# Thermostat_EEM_Breakout.net
KiCad netlist of a schematic drawn in Altium Designer
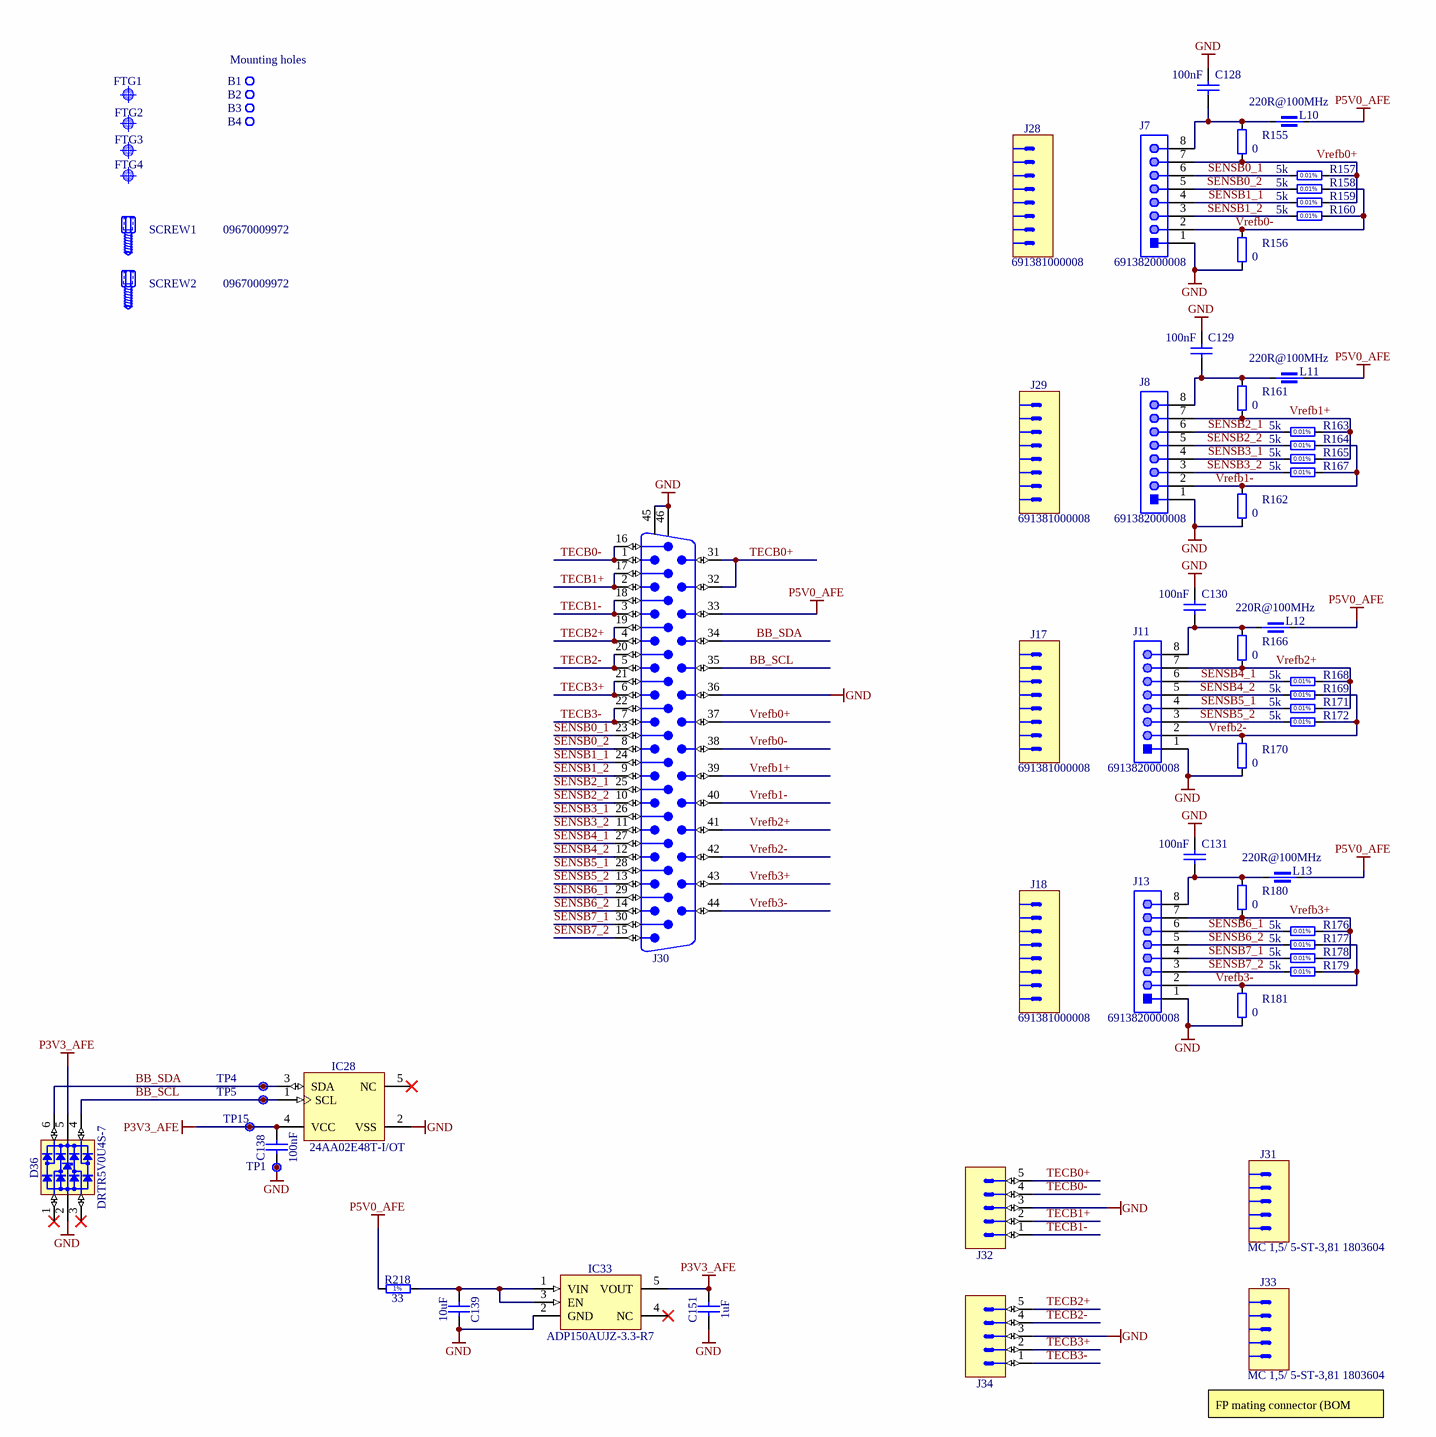
[diagram p0: Thermostat_EEM_Breakout.SchDoc]

(export (version "E")
  (design (tool "Eeschema 10.0.6"))
  (components
    (comp (ref "B1")
      (value "Plated Hole")
      (footprint "MTG320_550")
      (description "Single Terminal Socket")
      (fields (field (name "PART NUMBER") "PLATED_HOLE3.2_PAD5.5") (field (name "AUTHOR") "CERN DEM JMW"))
      (libsource (lib "Eletro-mechanical") (part "Single Terminal Socket"))
    )
    (comp (ref "B2")
      (value "Plated Hole")
      (footprint "MTG320_550")
      (description "Single Terminal Socket")
      (fields (field (name "PART NUMBER") "PLATED_HOLE3.2_PAD5.5") (field (name "AUTHOR") "CERN DEM JMW"))
      (libsource (lib "Eletro-mechanical") (part "Single Terminal Socket"))
    )
    (comp (ref "B3")
      (value "Plated Hole")
      (footprint "MTG320_550")
      (description "Single Terminal Socket")
      (fields (field (name "PART NUMBER") "PLATED_HOLE3.2_PAD5.5") (field (name "AUTHOR") "CERN DEM JMW"))
      (libsource (lib "Eletro-mechanical") (part "Single Terminal Socket"))
    )
    (comp (ref "B4")
      (value "Plated Hole")
      (footprint "MTG320_550")
      (description "Single Terminal Socket")
      (fields (field (name "PART NUMBER") "PLATED_HOLE3.2_PAD5.5") (field (name "AUTHOR") "CERN DEM JMW"))
      (libsource (lib "Eletro-mechanical") (part "Single Terminal Socket"))
    )
    (comp (ref "C128")
      (value "100nF")
      (footprint "CAPC1005X55N")
      (description "Non-polarised capacitor")
      (fields
        (field (name "PART NUMBER") "CC0402_100NF_16V_10%_X5R")
        (field (name "VOLTAGE") "16V")
        (field (name "AUTHOR") "CERN DEM JLC")
      )
      (libsource (lib "Capacitors") (part "Capacitor - non polarized"))
    )
    (comp (ref "C129")
      (value "100nF")
      (footprint "CAPC1005X55N")
      (description "Non-polarised capacitor")
      (fields
        (field (name "PART NUMBER") "CC0402_100NF_16V_10%_X5R")
        (field (name "VOLTAGE") "16V")
        (field (name "AUTHOR") "CERN DEM JLC")
      )
      (libsource (lib "Capacitors") (part "Capacitor - non polarized"))
    )
    (comp (ref "C130")
      (value "100nF")
      (footprint "CAPC1005X55N")
      (description "Non-polarised capacitor")
      (fields
        (field (name "PART NUMBER") "CC0402_100NF_16V_10%_X5R")
        (field (name "VOLTAGE") "16V")
        (field (name "AUTHOR") "CERN DEM JLC")
      )
      (libsource (lib "Capacitors") (part "Capacitor - non polarized"))
    )
    (comp (ref "C131")
      (value "100nF")
      (footprint "CAPC1005X55N")
      (description "Non-polarised capacitor")
      (fields
        (field (name "PART NUMBER") "CC0402_100NF_16V_10%_X5R")
        (field (name "VOLTAGE") "16V")
        (field (name "AUTHOR") "CERN DEM JLC")
      )
      (libsource (lib "Capacitors") (part "Capacitor - non polarized"))
    )
    (comp (ref "C138")
      (value "100nF")
      (footprint "CAPC1005X55N")
      (description "Non-polarised capacitor")
      (fields
        (field (name "PART NUMBER") "CC0402_100NF_16V_10%_X5R")
        (field (name "VOLTAGE") "16V")
        (field (name "AUTHOR") "CERN DEM JLC")
      )
      (libsource (lib "Capacitors") (part "Capacitor - non polarized"))
    )
    (comp (ref "C139")
      (value "10uF")
      (footprint "CAPC2012X135N")
      (description "Non-polarised capacitor")
      (fields
        (field (name "PART NUMBER") "CC0805_10UF_16V_10%_X5R")
        (field (name "VOLTAGE") "16V")
        (field (name "AUTHOR") "CERN DEM JLC")
      )
      (libsource (lib "Capacitors") (part "Capacitor - non polarized"))
    )
    (comp (ref "C151")
      (value "1uF")
      (footprint "CAPC1608X87N")
      (description "Non-polarised capacitor")
      (fields
        (field (name "PART NUMBER") "CC0603_1UF_25V_10%_X7R")
        (field (name "VOLTAGE") "25V")
        (field (name "AUTHOR") "CERN DEM JLC")
      )
      (libsource (lib "Capacitors") (part "Capacitor - non polarized"))
    )
    (comp (ref "D36")
      (value "DRTR5V0U4S-7")
      (footprint "SOT65P210X110-6N")
      (description "Integrated Quad Ultra-Low Capacitance ESD Protection")
      (fields (field (name "MANUFACTURER") "DIODES") (field (name "AUTHOR") "GK"))
      (libsource (lib "Diodes") (part "D_TVS_DRTR5V0U4S-7"))
    )
    (comp (ref "FTG1")
      (value "Use only in PCB")
      (footprint "FIDUCIAL_TOP_S100-200")
      (description "Fiducial Target")
      (fields (field (name "PART NUMBER") "FIDUCIAL_TARGET_S100-200") (field (name "AUTHOR") "CERN DEM JLC"))
      (libsource (lib "Eletro-mechanical") (part "Fiducial Target"))
    )
    (comp (ref "FTG2")
      (value "Use only in PCB")
      (footprint "FIDUCIAL_TOP_S100-200")
      (description "Fiducial Target")
      (fields (field (name "PART NUMBER") "FIDUCIAL_TARGET_S100-200") (field (name "AUTHOR") "CERN DEM JLC"))
      (libsource (lib "Eletro-mechanical") (part "Fiducial Target"))
    )
    (comp (ref "FTG3")
      (value "Use only in PCB")
      (footprint "FIDUCIAL_TOP_S100-200")
      (description "Fiducial Target")
      (fields (field (name "PART NUMBER") "FIDUCIAL_TARGET_S100-200") (field (name "AUTHOR") "CERN DEM JLC"))
      (libsource (lib "Eletro-mechanical") (part "Fiducial Target"))
    )
    (comp (ref "FTG4")
      (value "Use only in PCB")
      (footprint "FIDUCIAL_TOP_S100-200")
      (description "Fiducial Target")
      (fields (field (name "PART NUMBER") "FIDUCIAL_TARGET_S100-200") (field (name "AUTHOR") "CERN DEM JLC"))
      (libsource (lib "Eletro-mechanical") (part "Fiducial Target"))
    )
    (comp (ref "IC28")
      (value "24AA02E48T-I/OT")
      (footprint "SOT95P280X145-5N")
      (description "1.7V-5.5V, 2K I2C Serial EEPROM With EUI-48 Node Identity")
      (fields (field (name "MANUFACTURER") "MICROCHIP TECHNOLOGY") (field (name "AUTHOR") "CERN DEM MR"))
      (libsource (lib "ICs And Semiconductors") (part "24AA02E48T-I/OT"))
    )
    (comp (ref "IC33")
      (value "ADP150AUJZ-3.3-R7")
      (footprint "SOT95P280X90-5N")
      (description "Ultralow Noise, 150 mA CMOS Linear Regulator")
      (fields (field (name "MANUFACTURER") "ANALOG DEVICES") (field (name "AUTHOR") "CERN DEM JLC"))
      (libsource (lib "ICs And Semiconductors") (part "ADP150AUJZ"))
    )
    (comp (ref "J7")
      (value "691382000008")
      (footprint "691382000008")
      (description "WR-TBL Serie 382 Vertical PCB Header, Pluggable, pitch 2.5mm, 8p")
      (fields (field (name "PUBLISHER") "Wurth Elektronik"))
      (libsource (lib "Altium_WR-TBL (rev19a)") (part "691382000008"))
    )
    (comp (ref "J8")
      (value "691382000008")
      (footprint "691382000008")
      (description "WR-TBL Serie 382 Vertical PCB Header, Pluggable, pitch 2.5mm, 8p")
      (fields (field (name "PUBLISHER") "Wurth Elektronik"))
      (libsource (lib "Altium_WR-TBL (rev19a)") (part "691382000008"))
    )
    (comp (ref "J11")
      (value "691382000008")
      (footprint "691382000008")
      (description "WR-TBL Serie 382 Vertical PCB Header, Pluggable, pitch 2.5mm, 8p")
      (fields (field (name "PUBLISHER") "Wurth Elektronik"))
      (libsource (lib "Altium_WR-TBL (rev19a)") (part "691382000008"))
    )
    (comp (ref "J13")
      (value "691382000008")
      (footprint "691382000008")
      (description "WR-TBL Serie 382 Vertical PCB Header, Pluggable, pitch 2.5mm, 8p")
      (fields (field (name "PUBLISHER") "Wurth Elektronik"))
      (libsource (lib "Altium_WR-TBL (rev19a)") (part "691382000008"))
    )
    (comp (ref "J17")
      (value "691381000008")
      (footprint "WURTH_691381000008")
      (description "Phoenix Contact 2.5 pitch terminal plug, 8 ways")
      (fields (field (name "MANUFACTURER") "WURTH") (field (name "MANUFACTURER PART NUMBER") "691381000008"))
      (libsource (lib "Connectors") (part "CON_TB_WURTH_691381000008"))
    )
    (comp (ref "J18")
      (value "691381000008")
      (footprint "WURTH_691381000008")
      (description "Phoenix Contact 2.5 pitch terminal plug, 8 ways")
      (fields (field (name "MANUFACTURER") "WURTH") (field (name "MANUFACTURER PART NUMBER") "691381000008"))
      (libsource (lib "Connectors") (part "CON_TB_WURTH_691381000008"))
    )
    (comp (ref "J28")
      (value "691381000008")
      (footprint "WURTH_691381000008")
      (description "Phoenix Contact 2.5 pitch terminal plug, 8 ways")
      (fields (field (name "MANUFACTURER") "WURTH") (field (name "MANUFACTURER PART NUMBER") "691381000008"))
      (libsource (lib "Connectors") (part "CON_TB_WURTH_691381000008"))
    )
    (comp (ref "J29")
      (value "691381000008")
      (footprint "WURTH_691381000008")
      (description "Phoenix Contact 2.5 pitch terminal plug, 8 ways")
      (fields (field (name "MANUFACTURER") "WURTH") (field (name "MANUFACTURER PART NUMBER") "691381000008"))
      (libsource (lib "Connectors") (part "CON_TB_WURTH_691381000008"))
    )
    (comp (ref "J30")
      (value "D-Sub")
      (footprint "AMPHENOL_10090926-P444XLF")
      (description "Connector D-sub 44 Male")
      (fields
        (field (name "PART NUMBER") "AMPHENOL_10090926-P444XLF")
        (field (name "MANUFACTURER") "AMPHENOL")
        (field (name "AUTHOR") "CERN DEM BC")
      )
      (libsource (lib "Connectors") (part "Connector D-sub 44 Male"))
    )
    (comp (ref "J31")
      (value "~")
      (footprint "PHOENIX_1803604")
      (description "Phoenix Contact 3.81 pitch terminal plug, 5 ways")
      (fields
        (field (name "MANUFACTURER") "Phoenix Contact")
        (field (name "MANUFACTURER PART NUMBER") "MC 1,5/ 5-ST-3,81 1803604")
      )
      (libsource (lib "Connectors") (part "PHOENIX_1803604"))
    )
    (comp (ref "J32")
      (value "~")
      (footprint "PHOENIX_1803455")
      (description "Connector 5 Male")
      (fields
        (field (name "PART NUMBER") "PHOENIX_1803455")
        (field (name "MANUFACTURER") "PHOENIX CONTACT")
        (field (name "AUTHOR") "CERN DEM JLC")
      )
      (libsource (lib "Connectors") (part "Connector 5 Male"))
    )
    (comp (ref "J33")
      (value "~")
      (footprint "PHOENIX_1803604")
      (description "Phoenix Contact 3.81 pitch terminal plug, 5 ways")
      (fields
        (field (name "MANUFACTURER") "Phoenix Contact")
        (field (name "MANUFACTURER PART NUMBER") "MC 1,5/ 5-ST-3,81 1803604")
      )
      (libsource (lib "Connectors") (part "PHOENIX_1803604"))
    )
    (comp (ref "J34")
      (value "~")
      (footprint "PHOENIX_1803455")
      (description "Connector 5 Male")
      (fields
        (field (name "PART NUMBER") "PHOENIX_1803455")
        (field (name "MANUFACTURER") "PHOENIX CONTACT")
        (field (name "AUTHOR") "CERN DEM JLC")
      )
      (libsource (lib "Connectors") (part "Connector 5 Male"))
    )
    (comp (ref "L10")
      (value "220R@100MHz")
      (footprint "INDC1005X55N")
      (fields
        (field (name "PART NUMBER") "IND0402_MURATA_BLM15HB221SN1")
        (field (name "POWER") "250mA")
        (field (name "TOLERANCE") "±25%")
        (field (name "AUTHOR") "CERN DEM JLC")
      )
      (libsource (lib "Inductors & Transformers") (part "Ferrite Bead"))
    )
    (comp (ref "L11")
      (value "220R@100MHz")
      (footprint "INDC1005X55N")
      (fields
        (field (name "PART NUMBER") "IND0402_MURATA_BLM15HB221SN1")
        (field (name "POWER") "250mA")
        (field (name "TOLERANCE") "±25%")
        (field (name "AUTHOR") "CERN DEM JLC")
      )
      (libsource (lib "Inductors & Transformers") (part "Ferrite Bead"))
    )
    (comp (ref "L12")
      (value "220R@100MHz")
      (footprint "INDC1005X55N")
      (fields
        (field (name "PART NUMBER") "IND0402_MURATA_BLM15HB221SN1")
        (field (name "POWER") "250mA")
        (field (name "TOLERANCE") "±25%")
        (field (name "AUTHOR") "CERN DEM JLC")
      )
      (libsource (lib "Inductors & Transformers") (part "Ferrite Bead"))
    )
    (comp (ref "L13")
      (value "220R@100MHz")
      (footprint "INDC1005X55N")
      (fields
        (field (name "PART NUMBER") "IND0402_MURATA_BLM15HB221SN1")
        (field (name "POWER") "250mA")
        (field (name "TOLERANCE") "±25%")
        (field (name "AUTHOR") "CERN DEM JLC")
      )
      (libsource (lib "Inductors & Transformers") (part "Ferrite Bead"))
    )
    (comp (ref "R155")
      (value "0")
      (footprint "RESC1608X55N")
      (description "Resistor")
      (fields
        (field (name "PART NUMBER") "R0603_0R_JUMPER")
        (field (name "MANUFACTURER") "GENERIC")
        (field (name "AUTHOR") "CERN DEM JLC")
      )
      (libsource (lib "Resistors") (part "Resistor"))
    )
    (comp (ref "R156")
      (value "0")
      (footprint "RESC1608X55N")
      (description "Resistor")
      (fields
        (field (name "PART NUMBER") "R0603_0R_JUMPER")
        (field (name "MANUFACTURER") "GENERIC")
        (field (name "AUTHOR") "CERN DEM JLC")
      )
      (libsource (lib "Resistors") (part "Resistor"))
    )
    (comp (ref "R157")
      (value "5k")
      (footprint "RESC2013X64N")
      (description "Resistor - 0.01%")
      (fields
        (field (name "PART NUMBER") "R0805_5K_0.01%_0.2W_0.2PPM_VISHAY_VSMP")
        (field (name "POWER") "0.2W")
        (field (name "AUTHOR") "CERN DEM JLC")
      )
      (libsource (lib "Resistors") (part "Resistor - 0.01%"))
    )
    (comp (ref "R158")
      (value "5k")
      (footprint "RESC2013X64N")
      (description "Resistor - 0.01%")
      (fields
        (field (name "PART NUMBER") "R0805_5K_0.01%_0.2W_0.2PPM_VISHAY_VSMP")
        (field (name "POWER") "0.2W")
        (field (name "AUTHOR") "CERN DEM JLC")
      )
      (libsource (lib "Resistors") (part "Resistor - 0.01%"))
    )
    (comp (ref "R159")
      (value "5k")
      (footprint "RESC2013X64N")
      (description "Resistor - 0.01%")
      (fields
        (field (name "PART NUMBER") "R0805_5K_0.01%_0.2W_0.2PPM_VISHAY_VSMP")
        (field (name "POWER") "0.2W")
        (field (name "AUTHOR") "CERN DEM JLC")
      )
      (libsource (lib "Resistors") (part "Resistor - 0.01%"))
    )
    (comp (ref "R160")
      (value "5k")
      (footprint "RESC2013X64N")
      (description "Resistor - 0.01%")
      (fields
        (field (name "PART NUMBER") "R0805_5K_0.01%_0.2W_0.2PPM_VISHAY_VSMP")
        (field (name "POWER") "0.2W")
        (field (name "AUTHOR") "CERN DEM JLC")
      )
      (libsource (lib "Resistors") (part "Resistor - 0.01%"))
    )
    (comp (ref "R161")
      (value "0")
      (footprint "RESC1608X55N")
      (description "Resistor")
      (fields
        (field (name "PART NUMBER") "R0603_0R_JUMPER")
        (field (name "MANUFACTURER") "GENERIC")
        (field (name "AUTHOR") "CERN DEM JLC")
      )
      (libsource (lib "Resistors") (part "Resistor"))
    )
    (comp (ref "R162")
      (value "0")
      (footprint "RESC1608X55N")
      (description "Resistor")
      (fields
        (field (name "PART NUMBER") "R0603_0R_JUMPER")
        (field (name "MANUFACTURER") "GENERIC")
        (field (name "AUTHOR") "CERN DEM JLC")
      )
      (libsource (lib "Resistors") (part "Resistor"))
    )
    (comp (ref "R163")
      (value "5k")
      (footprint "RESC2013X64N")
      (description "Resistor - 0.01%")
      (fields
        (field (name "PART NUMBER") "R0805_5K_0.01%_0.2W_0.2PPM_VISHAY_VSMP")
        (field (name "POWER") "0.2W")
        (field (name "AUTHOR") "CERN DEM JLC")
      )
      (libsource (lib "Resistors") (part "Resistor - 0.01%"))
    )
    (comp (ref "R164")
      (value "5k")
      (footprint "RESC2013X64N")
      (description "Resistor - 0.01%")
      (fields
        (field (name "PART NUMBER") "R0805_5K_0.01%_0.2W_0.2PPM_VISHAY_VSMP")
        (field (name "POWER") "0.2W")
        (field (name "AUTHOR") "CERN DEM JLC")
      )
      (libsource (lib "Resistors") (part "Resistor - 0.01%"))
    )
    (comp (ref "R165")
      (value "5k")
      (footprint "RESC2013X64N")
      (description "Resistor - 0.01%")
      (fields
        (field (name "PART NUMBER") "R0805_5K_0.01%_0.2W_0.2PPM_VISHAY_VSMP")
        (field (name "POWER") "0.2W")
        (field (name "AUTHOR") "CERN DEM JLC")
      )
      (libsource (lib "Resistors") (part "Resistor - 0.01%"))
    )
    (comp (ref "R166")
      (value "0")
      (footprint "RESC1608X55N")
      (description "Resistor")
      (fields
        (field (name "PART NUMBER") "R0603_0R_JUMPER")
        (field (name "MANUFACTURER") "GENERIC")
        (field (name "AUTHOR") "CERN DEM JLC")
      )
      (libsource (lib "Resistors") (part "Resistor"))
    )
    (comp (ref "R167")
      (value "5k")
      (footprint "RESC2013X64N")
      (description "Resistor - 0.01%")
      (fields
        (field (name "PART NUMBER") "R0805_5K_0.01%_0.2W_0.2PPM_VISHAY_VSMP")
        (field (name "POWER") "0.2W")
        (field (name "AUTHOR") "CERN DEM JLC")
      )
      (libsource (lib "Resistors") (part "Resistor - 0.01%"))
    )
    (comp (ref "R168")
      (value "5k")
      (footprint "RESC2013X64N")
      (description "Resistor - 0.01%")
      (fields
        (field (name "PART NUMBER") "R0805_5K_0.01%_0.2W_0.2PPM_VISHAY_VSMP")
        (field (name "POWER") "0.2W")
        (field (name "AUTHOR") "CERN DEM JLC")
      )
      (libsource (lib "Resistors") (part "Resistor - 0.01%"))
    )
    (comp (ref "R169")
      (value "5k")
      (footprint "RESC2013X64N")
      (description "Resistor - 0.01%")
      (fields
        (field (name "PART NUMBER") "R0805_5K_0.01%_0.2W_0.2PPM_VISHAY_VSMP")
        (field (name "POWER") "0.2W")
        (field (name "AUTHOR") "CERN DEM JLC")
      )
      (libsource (lib "Resistors") (part "Resistor - 0.01%"))
    )
    (comp (ref "R170")
      (value "0")
      (footprint "RESC1608X55N")
      (description "Resistor")
      (fields
        (field (name "PART NUMBER") "R0603_0R_JUMPER")
        (field (name "MANUFACTURER") "GENERIC")
        (field (name "AUTHOR") "CERN DEM JLC")
      )
      (libsource (lib "Resistors") (part "Resistor"))
    )
    (comp (ref "R171")
      (value "5k")
      (footprint "RESC2013X64N")
      (description "Resistor - 0.01%")
      (fields
        (field (name "PART NUMBER") "R0805_5K_0.01%_0.2W_0.2PPM_VISHAY_VSMP")
        (field (name "POWER") "0.2W")
        (field (name "AUTHOR") "CERN DEM JLC")
      )
      (libsource (lib "Resistors") (part "Resistor - 0.01%"))
    )
    (comp (ref "R172")
      (value "5k")
      (footprint "RESC2013X64N")
      (description "Resistor - 0.01%")
      (fields
        (field (name "PART NUMBER") "R0805_5K_0.01%_0.2W_0.2PPM_VISHAY_VSMP")
        (field (name "POWER") "0.2W")
        (field (name "AUTHOR") "CERN DEM JLC")
      )
      (libsource (lib "Resistors") (part "Resistor - 0.01%"))
    )
    (comp (ref "R176")
      (value "5k")
      (footprint "RESC2013X64N")
      (description "Resistor - 0.01%")
      (fields
        (field (name "PART NUMBER") "R0805_5K_0.01%_0.2W_0.2PPM_VISHAY_VSMP")
        (field (name "POWER") "0.2W")
        (field (name "AUTHOR") "CERN DEM JLC")
      )
      (libsource (lib "Resistors") (part "Resistor - 0.01%"))
    )
    (comp (ref "R177")
      (value "5k")
      (footprint "RESC2013X64N")
      (description "Resistor - 0.01%")
      (fields
        (field (name "PART NUMBER") "R0805_5K_0.01%_0.2W_0.2PPM_VISHAY_VSMP")
        (field (name "POWER") "0.2W")
        (field (name "AUTHOR") "CERN DEM JLC")
      )
      (libsource (lib "Resistors") (part "Resistor - 0.01%"))
    )
    (comp (ref "R178")
      (value "5k")
      (footprint "RESC2013X64N")
      (description "Resistor - 0.01%")
      (fields
        (field (name "PART NUMBER") "R0805_5K_0.01%_0.2W_0.2PPM_VISHAY_VSMP")
        (field (name "POWER") "0.2W")
        (field (name "AUTHOR") "CERN DEM JLC")
      )
      (libsource (lib "Resistors") (part "Resistor - 0.01%"))
    )
    (comp (ref "R179")
      (value "5k")
      (footprint "RESC2013X64N")
      (description "Resistor - 0.01%")
      (fields
        (field (name "PART NUMBER") "R0805_5K_0.01%_0.2W_0.2PPM_VISHAY_VSMP")
        (field (name "POWER") "0.2W")
        (field (name "AUTHOR") "CERN DEM JLC")
      )
      (libsource (lib "Resistors") (part "Resistor - 0.01%"))
    )
    (comp (ref "R180")
      (value "0")
      (footprint "RESC1608X55N")
      (description "Resistor")
      (fields
        (field (name "PART NUMBER") "R0603_0R_JUMPER")
        (field (name "MANUFACTURER") "GENERIC")
        (field (name "AUTHOR") "CERN DEM JLC")
      )
      (libsource (lib "Resistors") (part "Resistor"))
    )
    (comp (ref "R181")
      (value "0")
      (footprint "RESC1608X55N")
      (description "Resistor")
      (fields
        (field (name "PART NUMBER") "R0603_0R_JUMPER")
        (field (name "MANUFACTURER") "GENERIC")
        (field (name "AUTHOR") "CERN DEM JLC")
      )
      (libsource (lib "Resistors") (part "Resistor"))
    )
    (comp (ref "R218")
      (value "33")
      (footprint "RESC1005X40N")
      (description "Resistor - 1%")
      (fields
        (field (name "PART NUMBER") "R0402_33R_1%_0.0625W_100PPM")
        (field (name "POWER") "0.0625W")
        (field (name "AUTHOR") "CERN DEM JLC")
      )
      (libsource (lib "Resistors") (part "Resistor - 1%"))
    )
    (comp (ref "SCREW1")
      (value "09670009972")
      (footprint "3M_3341-31")
      (description "Female Screw Lock")
      (fields (field (name "MANUFACTURER") "HARTING") (field (name "AUTHOR") "GK"))
      (libsource (lib "Mechanical") (part "MECH_MDR_screw_lock"))
    )
    (comp (ref "SCREW2")
      (value "09670009972")
      (footprint "3M_3341-31")
      (description "Female Screw Lock")
      (fields (field (name "MANUFACTURER") "HARTING") (field (name "AUTHOR") "GK"))
      (libsource (lib "Mechanical") (part "MECH_MDR_screw_lock"))
    )
    (comp (ref "TP1")
      (value "Test Point")
      (footprint "TPS127")
      (fields (field (name "PART NUMBER") "SMD_PAD_1.27X1.27MM") (field (name "AUTHOR") "CERN DEM JLC"))
      (libsource (lib "Eletro-mechanical") (part "Test Point"))
    )
    (comp (ref "TP4")
      (value "Test Point")
      (footprint "TPS127")
      (fields (field (name "PART NUMBER") "SMD_PAD_1.27X1.27MM") (field (name "AUTHOR") "CERN DEM JLC"))
      (libsource (lib "Eletro-mechanical") (part "Test Point"))
    )
    (comp (ref "TP5")
      (value "Test Point")
      (footprint "TPS127")
      (fields (field (name "PART NUMBER") "SMD_PAD_1.27X1.27MM") (field (name "AUTHOR") "CERN DEM JLC"))
      (libsource (lib "Eletro-mechanical") (part "Test Point"))
    )
    (comp (ref "TP15")
      (value "Test Point")
      (footprint "TPS127")
      (fields (field (name "PART NUMBER") "SMD_PAD_1.27X1.27MM") (field (name "AUTHOR") "CERN DEM JLC"))
      (libsource (lib "Eletro-mechanical") (part "Test Point"))
    )
  )
  (nets
    (net (code "1") (name "/BB_SCL") (class "Default")
      (node (ref "D36") (pin "4") (pinfunction "I/O3_4") (pintype "bidirectional"))
      (node (ref "IC28") (pin "1") (pinfunction "SCL_1") (pintype "input"))
      (node (ref "J30") (pin "35") (pinfunction "35_35") (pintype "bidirectional"))
      (node (ref "TP5") (pin "1") (pinfunction "1_1") (pintype "bidirectional"))
    )
    (net (code "2") (name "/BB_SDA") (class "Default")
      (node (ref "D36") (pin "6") (pinfunction "I/O4_6") (pintype "bidirectional"))
      (node (ref "IC28") (pin "3") (pinfunction "SDA_3") (pintype "bidirectional"))
      (node (ref "J30") (pin "34") (pinfunction "34_34") (pintype "bidirectional"))
      (node (ref "TP4") (pin "1") (pinfunction "1_1") (pintype "bidirectional"))
    )
    (net (code "3") (name "/SENSB0_1") (class "Default")
      (node (ref "J30") (pin "23") (pinfunction "23_23") (pintype "bidirectional"))
      (node (ref "J7") (pin "6") (pinfunction "6_6") (pintype "passive"))
      (node (ref "R157") (pin "1") (pinfunction "1_1") (pintype "passive"))
    )
    (net (code "4") (name "/SENSB0_2") (class "Default")
      (node (ref "J30") (pin "8") (pinfunction "8_8") (pintype "bidirectional"))
      (node (ref "J7") (pin "5") (pinfunction "5_5") (pintype "passive"))
      (node (ref "R158") (pin "1") (pinfunction "1_1") (pintype "passive"))
    )
    (net (code "5") (name "/SENSB1_1") (class "Default")
      (node (ref "J30") (pin "24") (pinfunction "24_24") (pintype "bidirectional"))
      (node (ref "J7") (pin "4") (pinfunction "4_4") (pintype "passive"))
      (node (ref "R159") (pin "1") (pinfunction "1_1") (pintype "passive"))
    )
    (net (code "6") (name "/SENSB1_2") (class "Default")
      (node (ref "J30") (pin "9") (pinfunction "9_9") (pintype "bidirectional"))
      (node (ref "J7") (pin "3") (pinfunction "3_3") (pintype "passive"))
      (node (ref "R160") (pin "1") (pinfunction "1_1") (pintype "passive"))
    )
    (net (code "7") (name "/SENSB2_1") (class "Default")
      (node (ref "J30") (pin "25") (pinfunction "25_25") (pintype "bidirectional"))
      (node (ref "J8") (pin "6") (pinfunction "6_6") (pintype "passive"))
      (node (ref "R163") (pin "1") (pinfunction "1_1") (pintype "passive"))
    )
    (net (code "8") (name "/SENSB2_2") (class "Default")
      (node (ref "J30") (pin "10") (pinfunction "10_10") (pintype "bidirectional"))
      (node (ref "J8") (pin "5") (pinfunction "5_5") (pintype "passive"))
      (node (ref "R164") (pin "1") (pinfunction "1_1") (pintype "passive"))
    )
    (net (code "9") (name "/SENSB3_1") (class "Default")
      (node (ref "J30") (pin "26") (pinfunction "26_26") (pintype "bidirectional"))
      (node (ref "J8") (pin "4") (pinfunction "4_4") (pintype "passive"))
      (node (ref "R165") (pin "1") (pinfunction "1_1") (pintype "passive"))
    )
    (net (code "10") (name "/SENSB3_2") (class "Default")
      (node (ref "J30") (pin "11") (pinfunction "11_11") (pintype "bidirectional"))
      (node (ref "J8") (pin "3") (pinfunction "3_3") (pintype "passive"))
      (node (ref "R167") (pin "1") (pinfunction "1_1") (pintype "passive"))
    )
    (net (code "11") (name "/SENSB4_1") (class "Default")
      (node (ref "J11") (pin "6") (pinfunction "6_6") (pintype "passive"))
      (node (ref "J30") (pin "27") (pinfunction "27_27") (pintype "bidirectional"))
      (node (ref "R168") (pin "1") (pinfunction "1_1") (pintype "passive"))
    )
    (net (code "12") (name "/SENSB4_2") (class "Default")
      (node (ref "J11") (pin "5") (pinfunction "5_5") (pintype "passive"))
      (node (ref "J30") (pin "12") (pinfunction "12_12") (pintype "bidirectional"))
      (node (ref "R169") (pin "1") (pinfunction "1_1") (pintype "passive"))
    )
    (net (code "13") (name "/SENSB5_1") (class "Default")
      (node (ref "J11") (pin "4") (pinfunction "4_4") (pintype "passive"))
      (node (ref "J30") (pin "28") (pinfunction "28_28") (pintype "bidirectional"))
      (node (ref "R171") (pin "1") (pinfunction "1_1") (pintype "passive"))
    )
    (net (code "14") (name "/SENSB5_2") (class "Default")
      (node (ref "J11") (pin "3") (pinfunction "3_3") (pintype "passive"))
      (node (ref "J30") (pin "13") (pinfunction "13_13") (pintype "bidirectional"))
      (node (ref "R172") (pin "1") (pinfunction "1_1") (pintype "passive"))
    )
    (net (code "15") (name "/SENSB6_1") (class "Default")
      (node (ref "J13") (pin "6") (pinfunction "6_6") (pintype "passive"))
      (node (ref "J30") (pin "29") (pinfunction "29_29") (pintype "bidirectional"))
      (node (ref "R176") (pin "1") (pinfunction "1_1") (pintype "passive"))
    )
    (net (code "16") (name "/SENSB6_2") (class "Default")
      (node (ref "J13") (pin "5") (pinfunction "5_5") (pintype "passive"))
      (node (ref "J30") (pin "14") (pinfunction "14_14") (pintype "bidirectional"))
      (node (ref "R177") (pin "1") (pinfunction "1_1") (pintype "passive"))
    )
    (net (code "17") (name "/SENSB7_1") (class "Default")
      (node (ref "J13") (pin "4") (pinfunction "4_4") (pintype "passive"))
      (node (ref "J30") (pin "30") (pinfunction "30_30") (pintype "bidirectional"))
      (node (ref "R178") (pin "1") (pinfunction "1_1") (pintype "passive"))
    )
    (net (code "18") (name "/SENSB7_2") (class "Default")
      (node (ref "J13") (pin "3") (pinfunction "3_3") (pintype "passive"))
      (node (ref "J30") (pin "15") (pinfunction "15_15") (pintype "bidirectional"))
      (node (ref "R179") (pin "1") (pinfunction "1_1") (pintype "passive"))
    )
    (net (code "19") (name "/TECB0+") (class "Default")
      (node (ref "J30") (pin "31") (pinfunction "31_31") (pintype "bidirectional"))
      (node (ref "J30") (pin "32") (pinfunction "32_32") (pintype "bidirectional"))
      (node (ref "J32") (pin "5") (pinfunction "5_5") (pintype "bidirectional"))
    )
    (net (code "20") (name "/TECB0-") (class "Default")
      (node (ref "J30") (pin "1") (pinfunction "1_1") (pintype "bidirectional"))
      (node (ref "J30") (pin "16") (pinfunction "16_16") (pintype "bidirectional"))
      (node (ref "J32") (pin "4") (pinfunction "4_4") (pintype "bidirectional"))
    )
    (net (code "21") (name "/TECB1+") (class "Default")
      (node (ref "J30") (pin "17") (pinfunction "17_17") (pintype "bidirectional"))
      (node (ref "J30") (pin "2") (pinfunction "2_2") (pintype "bidirectional"))
      (node (ref "J32") (pin "2") (pinfunction "2_2") (pintype "bidirectional"))
    )
    (net (code "22") (name "/TECB1-") (class "Default")
      (node (ref "J30") (pin "18") (pinfunction "18_18") (pintype "bidirectional"))
      (node (ref "J30") (pin "3") (pinfunction "3_3") (pintype "bidirectional"))
      (node (ref "J32") (pin "1") (pinfunction "1_1") (pintype "bidirectional"))
    )
    (net (code "23") (name "/TECB2+") (class "Default")
      (node (ref "J30") (pin "19") (pinfunction "19_19") (pintype "bidirectional"))
      (node (ref "J30") (pin "4") (pinfunction "4_4") (pintype "bidirectional"))
      (node (ref "J34") (pin "5") (pinfunction "5_5") (pintype "bidirectional"))
    )
    (net (code "24") (name "/TECB2-") (class "Default")
      (node (ref "J30") (pin "20") (pinfunction "20_20") (pintype "bidirectional"))
      (node (ref "J30") (pin "5") (pinfunction "5_5") (pintype "bidirectional"))
      (node (ref "J34") (pin "4") (pinfunction "4_4") (pintype "bidirectional"))
    )
    (net (code "25") (name "/TECB3+") (class "Default")
      (node (ref "J30") (pin "21") (pinfunction "21_21") (pintype "bidirectional"))
      (node (ref "J30") (pin "6") (pinfunction "6_6") (pintype "bidirectional"))
      (node (ref "J34") (pin "2") (pinfunction "2_2") (pintype "bidirectional"))
    )
    (net (code "26") (name "/TECB3-") (class "Default")
      (node (ref "J30") (pin "22") (pinfunction "22_22") (pintype "bidirectional"))
      (node (ref "J30") (pin "7") (pinfunction "7_7") (pintype "bidirectional"))
      (node (ref "J34") (pin "1") (pinfunction "1_1") (pintype "bidirectional"))
    )
    (net (code "27") (name "/Vrefb0+") (class "Default")
      (node (ref "J30") (pin "37") (pinfunction "37_37") (pintype "bidirectional"))
      (node (ref "J7") (pin "7") (pinfunction "7_7") (pintype "passive"))
      (node (ref "R155") (pin "1") (pinfunction "1_1") (pintype "passive"))
      (node (ref "R157") (pin "2") (pinfunction "2_2") (pintype "passive"))
      (node (ref "R159") (pin "2") (pinfunction "2_2") (pintype "passive"))
    )
    (net (code "28") (name "/Vrefb0-") (class "Default")
      (node (ref "J30") (pin "38") (pinfunction "38_38") (pintype "bidirectional"))
      (node (ref "J7") (pin "2") (pinfunction "2_2") (pintype "passive"))
      (node (ref "R156") (pin "2") (pinfunction "2_2") (pintype "passive"))
      (node (ref "R158") (pin "2") (pinfunction "2_2") (pintype "passive"))
      (node (ref "R160") (pin "2") (pinfunction "2_2") (pintype "passive"))
    )
    (net (code "29") (name "/Vrefb1+") (class "Default")
      (node (ref "J30") (pin "39") (pinfunction "39_39") (pintype "bidirectional"))
      (node (ref "J8") (pin "7") (pinfunction "7_7") (pintype "passive"))
      (node (ref "R161") (pin "1") (pinfunction "1_1") (pintype "passive"))
      (node (ref "R163") (pin "2") (pinfunction "2_2") (pintype "passive"))
      (node (ref "R165") (pin "2") (pinfunction "2_2") (pintype "passive"))
    )
    (net (code "30") (name "/Vrefb1-") (class "Default")
      (node (ref "J30") (pin "40") (pinfunction "40_40") (pintype "bidirectional"))
      (node (ref "J8") (pin "2") (pinfunction "2_2") (pintype "passive"))
      (node (ref "R162") (pin "2") (pinfunction "2_2") (pintype "passive"))
      (node (ref "R164") (pin "2") (pinfunction "2_2") (pintype "passive"))
      (node (ref "R167") (pin "2") (pinfunction "2_2") (pintype "passive"))
    )
    (net (code "31") (name "/Vrefb2+") (class "Default")
      (node (ref "J11") (pin "7") (pinfunction "7_7") (pintype "passive"))
      (node (ref "J30") (pin "41") (pinfunction "41_41") (pintype "bidirectional"))
      (node (ref "R166") (pin "1") (pinfunction "1_1") (pintype "passive"))
      (node (ref "R168") (pin "2") (pinfunction "2_2") (pintype "passive"))
      (node (ref "R171") (pin "2") (pinfunction "2_2") (pintype "passive"))
    )
    (net (code "32") (name "/Vrefb2-") (class "Default")
      (node (ref "J11") (pin "2") (pinfunction "2_2") (pintype "passive"))
      (node (ref "J30") (pin "42") (pinfunction "42_42") (pintype "bidirectional"))
      (node (ref "R169") (pin "2") (pinfunction "2_2") (pintype "passive"))
      (node (ref "R170") (pin "2") (pinfunction "2_2") (pintype "passive"))
      (node (ref "R172") (pin "2") (pinfunction "2_2") (pintype "passive"))
    )
    (net (code "33") (name "/Vrefb3+") (class "Default")
      (node (ref "J13") (pin "7") (pinfunction "7_7") (pintype "passive"))
      (node (ref "J30") (pin "43") (pinfunction "43_43") (pintype "bidirectional"))
      (node (ref "R176") (pin "2") (pinfunction "2_2") (pintype "passive"))
      (node (ref "R178") (pin "2") (pinfunction "2_2") (pintype "passive"))
      (node (ref "R180") (pin "1") (pinfunction "1_1") (pintype "passive"))
    )
    (net (code "34") (name "/Vrefb3-") (class "Default")
      (node (ref "J13") (pin "2") (pinfunction "2_2") (pintype "passive"))
      (node (ref "J30") (pin "44") (pinfunction "44_44") (pintype "bidirectional"))
      (node (ref "R177") (pin "2") (pinfunction "2_2") (pintype "passive"))
      (node (ref "R179") (pin "2") (pinfunction "2_2") (pintype "passive"))
      (node (ref "R181") (pin "2") (pinfunction "2_2") (pintype "passive"))
    )
    (net (code "35") (name "GND") (class "Default")
      (node (ref "C128") (pin "1") (pinfunction "1_1") (pintype "passive"))
      (node (ref "C129") (pin "1") (pinfunction "1_1") (pintype "passive"))
      (node (ref "C130") (pin "1") (pinfunction "1_1") (pintype "passive"))
      (node (ref "C131") (pin "1") (pinfunction "1_1") (pintype "passive"))
      (node (ref "C138") (pin "1") (pinfunction "1_1") (pintype "passive"))
      (node (ref "C139") (pin "2") (pinfunction "2_2") (pintype "passive"))
      (node (ref "C151") (pin "1") (pinfunction "1_1") (pintype "passive"))
      (node (ref "D36") (pin "2") (pinfunction "GND_2") (pintype "power_in"))
      (node (ref "IC28") (pin "2") (pinfunction "VSS_2") (pintype "power_in"))
      (node (ref "IC33") (pin "2") (pinfunction "GND_2") (pintype "power_in"))
      (node (ref "J11") (pin "1") (pinfunction "1_1") (pintype "passive"))
      (node (ref "J13") (pin "1") (pinfunction "1_1") (pintype "passive"))
      (node (ref "J30") (pin "36") (pinfunction "36_36") (pintype "bidirectional"))
      (node (ref "J30") (pin "45") (pinfunction "45_45") (pintype "passive"))
      (node (ref "J30") (pin "46") (pinfunction "46_46") (pintype "passive"))
      (node (ref "J32") (pin "3") (pinfunction "3_3") (pintype "bidirectional"))
      (node (ref "J34") (pin "3") (pinfunction "3_3") (pintype "bidirectional"))
      (node (ref "J7") (pin "1") (pinfunction "1_1") (pintype "passive"))
      (node (ref "J8") (pin "1") (pinfunction "1_1") (pintype "passive"))
      (node (ref "R156") (pin "1") (pinfunction "1_1") (pintype "passive"))
      (node (ref "R162") (pin "1") (pinfunction "1_1") (pintype "passive"))
      (node (ref "R170") (pin "1") (pinfunction "1_1") (pintype "passive"))
      (node (ref "R181") (pin "1") (pinfunction "1_1") (pintype "passive"))
      (node (ref "TP1") (pin "1") (pinfunction "1_1") (pintype "bidirectional"))
    )
    (net (code "36") (name "Net-(C128-Pad2)") (class "Default")
      (node (ref "C128") (pin "2") (pinfunction "2_2") (pintype "passive"))
      (node (ref "J7") (pin "8") (pinfunction "8_8") (pintype "passive"))
      (node (ref "L10") (pin "1") (pinfunction "1_1") (pintype "passive"))
      (node (ref "R155") (pin "2") (pinfunction "2_2") (pintype "passive"))
    )
    (net (code "37") (name "Net-(C129-Pad2)") (class "Default")
      (node (ref "C129") (pin "2") (pinfunction "2_2") (pintype "passive"))
      (node (ref "J8") (pin "8") (pinfunction "8_8") (pintype "passive"))
      (node (ref "L11") (pin "1") (pinfunction "1_1") (pintype "passive"))
      (node (ref "R161") (pin "2") (pinfunction "2_2") (pintype "passive"))
    )
    (net (code "38") (name "Net-(C130-Pad2)") (class "Default")
      (node (ref "C130") (pin "2") (pinfunction "2_2") (pintype "passive"))
      (node (ref "J11") (pin "8") (pinfunction "8_8") (pintype "passive"))
      (node (ref "L12") (pin "1") (pinfunction "1_1") (pintype "passive"))
      (node (ref "R166") (pin "2") (pinfunction "2_2") (pintype "passive"))
    )
    (net (code "39") (name "Net-(C131-Pad2)") (class "Default")
      (node (ref "C131") (pin "2") (pinfunction "2_2") (pintype "passive"))
      (node (ref "J13") (pin "8") (pinfunction "8_8") (pintype "passive"))
      (node (ref "L13") (pin "1") (pinfunction "1_1") (pintype "passive"))
      (node (ref "R180") (pin "2") (pinfunction "2_2") (pintype "passive"))
    )
    (net (code "40") (name "Net-(IC33-EN)") (class "Default")
      (node (ref "C139") (pin "1") (pinfunction "1_1") (pintype "passive"))
      (node (ref "IC33") (pin "1") (pinfunction "VIN_1") (pintype "input"))
      (node (ref "IC33") (pin "3") (pinfunction "EN_3") (pintype "input"))
      (node (ref "R218") (pin "2") (pinfunction "2_2") (pintype "passive"))
    )
    (net (code "41") (name "P3V3_AFE") (class "Default")
      (node (ref "C138") (pin "2") (pinfunction "2_2") (pintype "passive"))
      (node (ref "C151") (pin "2") (pinfunction "2_2") (pintype "passive"))
      (node (ref "D36") (pin "5") (pinfunction "VBUS_5") (pintype "power_in"))
      (node (ref "IC28") (pin "4") (pinfunction "VCC_4") (pintype "power_in"))
      (node (ref "IC33") (pin "5") (pinfunction "VOUT_5") (pintype "power_in"))
      (node (ref "TP15") (pin "1") (pinfunction "1_1") (pintype "bidirectional"))
    )
    (net (code "42") (name "P5V0_AFE") (class "Default")
      (node (ref "J30") (pin "33") (pinfunction "33_33") (pintype "bidirectional"))
      (node (ref "L10") (pin "2") (pinfunction "2_2") (pintype "passive"))
      (node (ref "L11") (pin "2") (pinfunction "2_2") (pintype "passive"))
      (node (ref "L12") (pin "2") (pinfunction "2_2") (pintype "passive"))
      (node (ref "L13") (pin "2") (pinfunction "2_2") (pintype "passive"))
      (node (ref "R218") (pin "1") (pinfunction "1_1") (pintype "passive"))
    )
    (net (code "43") (name "unconnected-(B1-Pad1)") (class "Default")
      (node (ref "B1") (pin "1") (pinfunction "1_1") (pintype "bidirectional"))
    )
    (net (code "44") (name "unconnected-(B2-Pad1)") (class "Default")
      (node (ref "B2") (pin "1") (pinfunction "1_1") (pintype "bidirectional"))
    )
    (net (code "45") (name "unconnected-(B3-Pad1)") (class "Default")
      (node (ref "B3") (pin "1") (pinfunction "1_1") (pintype "bidirectional"))
    )
    (net (code "46") (name "unconnected-(B4-Pad1)") (class "Default")
      (node (ref "B4") (pin "1") (pinfunction "1_1") (pintype "bidirectional"))
    )
    (net (code "47") (name "unconnected-(D36-I{slash}O1-Pad1)") (class "Default")
      (node (ref "D36") (pin "1") (pinfunction "I/O1_1") (pintype "bidirectional+no_connect"))
    )
    (net (code "48") (name "unconnected-(D36-I{slash}O2-Pad3)") (class "Default")
      (node (ref "D36") (pin "3") (pinfunction "I/O2_3") (pintype "bidirectional+no_connect"))
    )
    (net (code "49") (name "unconnected-(IC28-NC-Pad5)") (class "Default")
      (node (ref "IC28") (pin "5") (pinfunction "NC_5") (pintype "passive+no_connect"))
    )
    (net (code "50") (name "unconnected-(IC33-NC-Pad4)") (class "Default")
      (node (ref "IC33") (pin "4") (pinfunction "NC_4") (pintype "passive+no_connect"))
    )
  )
)
